# 2012_Carte_Factorisee.net
KiCad netlist of a schematic drawn in Altium Designer
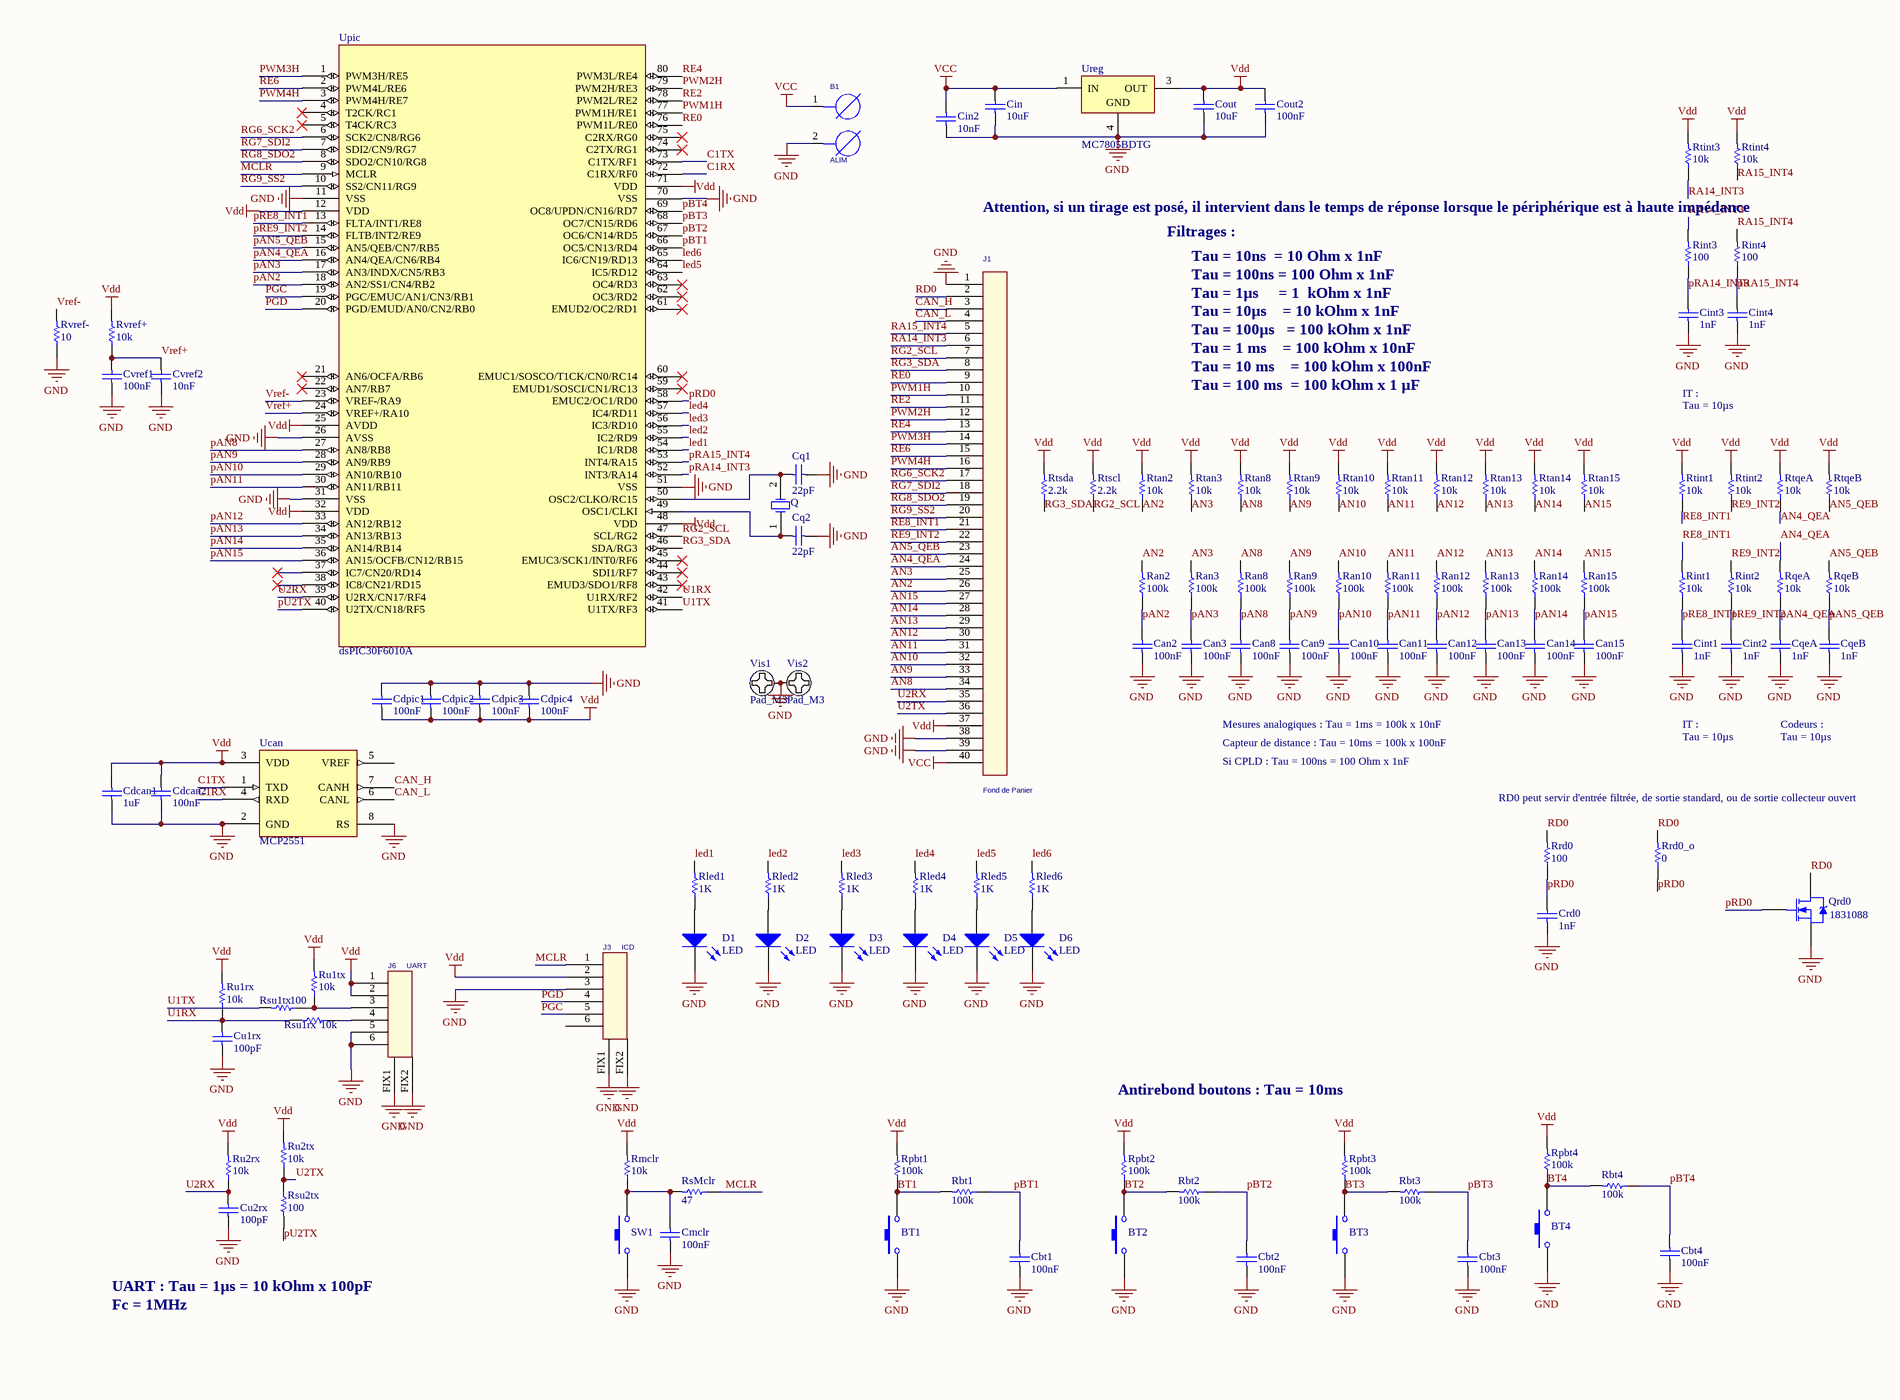
[diagram p0: 2012_Carte_Factorisee.SchDoc, left]
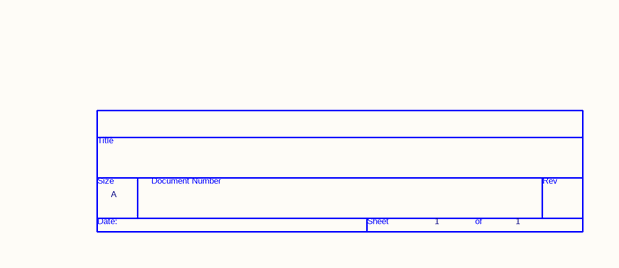
[diagram p1: 2012_Carte_Factorisee.SchDoc, right]

(export (version "E")
  (design (tool "Eeschema 10.0.6"))
  (components
    (comp (ref "*")
      (value "TitleBlock0")
      (fields (field (name "PAGE COUNT") "1") (field (name "PAGE NUMBER") "1") (field (name "PAGE SIZE") "A"))
      (libsource (lib "*") (part "TitleBlock0"))
    )
    (comp (ref "B1") (value "ALIM") (footprint "BORNIER2") (libsource (lib "*") (part "BORNIER2")))
    (comp (ref "BT1")
      (value "SW_Pushbutton_6x6mm_Vertical")
      (footprint "Switch 6x6 Vertical")
      (description "Switch tactil 6mm x 6mm Vertical")
      (libsource (lib "DG_Interrupteur") (part "SW_Pushbutton_6x6mm_Vertical"))
    )
    (comp (ref "BT2")
      (value "SW_Pushbutton_6x6mm_Vertical")
      (footprint "Switch 6x6 Vertical")
      (description "Switch tactil 6mm x 6mm Vertical")
      (libsource (lib "DG_Interrupteur") (part "SW_Pushbutton_6x6mm_Vertical"))
    )
    (comp (ref "BT3")
      (value "SW_Pushbutton_6x6mm_Vertical")
      (footprint "Switch 6x6 Vertical")
      (description "Switch tactil 6mm x 6mm Vertical")
      (libsource (lib "DG_Interrupteur") (part "SW_Pushbutton_6x6mm_Vertical"))
    )
    (comp (ref "BT4")
      (value "SW_Pushbutton_6x6mm_Vertical")
      (footprint "Switch 6x6 Vertical")
      (description "Switch tactil 6mm x 6mm Vertical")
      (libsource (lib "DG_Interrupteur") (part "SW_Pushbutton_6x6mm_Vertical"))
    )
    (comp (ref "Can2")
      (value "100nF")
      (footprint "C0805_N")
      (description "Capacitor")
      (libsource (lib "DG_Condensateur") (part "Capacitor"))
    )
    (comp (ref "Can3")
      (value "100nF")
      (footprint "C0805_N")
      (description "Capacitor")
      (libsource (lib "DG_Condensateur") (part "Capacitor"))
    )
    (comp (ref "Can8")
      (value "100nF")
      (footprint "C0805_N")
      (description "Capacitor")
      (libsource (lib "DG_Condensateur") (part "Capacitor"))
    )
    (comp (ref "Can9")
      (value "100nF")
      (footprint "C0805_N")
      (description "Capacitor")
      (libsource (lib "DG_Condensateur") (part "Capacitor"))
    )
    (comp (ref "Can10")
      (value "100nF")
      (footprint "C0805_N")
      (description "Capacitor")
      (libsource (lib "DG_Condensateur") (part "Capacitor"))
    )
    (comp (ref "Can11")
      (value "100nF")
      (footprint "C0805_N")
      (description "Capacitor")
      (libsource (lib "DG_Condensateur") (part "Capacitor"))
    )
    (comp (ref "Can12")
      (value "100nF")
      (footprint "C0805_N")
      (description "Capacitor")
      (libsource (lib "DG_Condensateur") (part "Capacitor"))
    )
    (comp (ref "Can13")
      (value "100nF")
      (footprint "C0805_N")
      (description "Capacitor")
      (libsource (lib "DG_Condensateur") (part "Capacitor"))
    )
    (comp (ref "Can14")
      (value "100nF")
      (footprint "C0805_N")
      (description "Capacitor")
      (libsource (lib "DG_Condensateur") (part "Capacitor"))
    )
    (comp (ref "Can15")
      (value "100nF")
      (footprint "C0805_N")
      (description "Capacitor")
      (libsource (lib "DG_Condensateur") (part "Capacitor"))
    )
    (comp (ref "Cbt1")
      (value "100nF")
      (footprint "C0805_N")
      (description "Capacitor")
      (libsource (lib "DG_Condensateur") (part "Capacitor"))
    )
    (comp (ref "Cbt2")
      (value "100nF")
      (footprint "C0805_N")
      (description "Capacitor")
      (libsource (lib "DG_Condensateur") (part "Capacitor"))
    )
    (comp (ref "Cbt3")
      (value "100nF")
      (footprint "C0805_N")
      (description "Capacitor")
      (libsource (lib "DG_Condensateur") (part "Capacitor"))
    )
    (comp (ref "Cbt4")
      (value "100nF")
      (footprint "C0805_N")
      (description "Capacitor")
      (libsource (lib "DG_Condensateur") (part "Capacitor"))
    )
    (comp (ref "Cdcan1")
      (value "1uF")
      (footprint "C1206_N")
      (description "Capacitor")
      (libsource (lib "DG_Condensateur") (part "Capacitor"))
    )
    (comp (ref "Cdcan2")
      (value "100nF")
      (footprint "C0805_N")
      (description "Capacitor")
      (libsource (lib "DG_Condensateur") (part "Capacitor"))
    )
    (comp (ref "Cdpic1")
      (value "100nF")
      (footprint "C0805_N")
      (description "Capacitor")
      (libsource (lib "DG_Condensateur") (part "Capacitor"))
    )
    (comp (ref "Cdpic2")
      (value "100nF")
      (footprint "C0805_N")
      (description "Capacitor")
      (libsource (lib "DG_Condensateur") (part "Capacitor"))
    )
    (comp (ref "Cdpic3")
      (value "100nF")
      (footprint "C0805_N")
      (description "Capacitor")
      (libsource (lib "DG_Condensateur") (part "Capacitor"))
    )
    (comp (ref "Cdpic4")
      (value "100nF")
      (footprint "C0805_N")
      (description "Capacitor")
      (libsource (lib "DG_Condensateur") (part "Capacitor"))
    )
    (comp (ref "Cin")
      (value "10uF")
      (footprint "C1206_N")
      (description "Capacitor")
      (libsource (lib "DG_Condensateur") (part "Capacitor"))
    )
    (comp (ref "Cin2")
      (value "10nF")
      (footprint "C0805_N")
      (description "Capacitor")
      (libsource (lib "DG_Condensateur") (part "Capacitor"))
    )
    (comp (ref "Cint1")
      (value "1nF")
      (footprint "C0805_N")
      (description "Capacitor")
      (libsource (lib "DG_Condensateur") (part "Capacitor"))
    )
    (comp (ref "Cint2")
      (value "1nF")
      (footprint "C0805_N")
      (description "Capacitor")
      (libsource (lib "DG_Condensateur") (part "Capacitor"))
    )
    (comp (ref "Cint3")
      (value "1nF")
      (footprint "C0805_N")
      (description "Capacitor")
      (libsource (lib "DG_Condensateur") (part "Capacitor"))
    )
    (comp (ref "Cint4")
      (value "1nF")
      (footprint "C0805_N")
      (description "Capacitor")
      (libsource (lib "DG_Condensateur") (part "Capacitor"))
    )
    (comp (ref "Cmclr")
      (value "100nF")
      (footprint "C0805_N")
      (description "Capacitor")
      (libsource (lib "DG_Condensateur") (part "Capacitor"))
    )
    (comp (ref "Cout")
      (value "10uF")
      (footprint "C1206_N")
      (description "Capacitor")
      (libsource (lib "DG_Condensateur") (part "Capacitor"))
    )
    (comp (ref "Cout2")
      (value "100nF")
      (footprint "C0805_N")
      (description "Capacitor")
      (libsource (lib "DG_Condensateur") (part "Capacitor"))
    )
    (comp (ref "Cq1")
      (value "22pF")
      (footprint "C0805_N")
      (description "Capacitor")
      (libsource (lib "DG_Condensateur") (part "Capacitor"))
    )
    (comp (ref "Cq2")
      (value "22pF")
      (footprint "C0805_N")
      (description "Capacitor")
      (libsource (lib "DG_Condensateur") (part "Capacitor"))
    )
    (comp (ref "CqeA")
      (value "1nF")
      (footprint "C0805_N")
      (description "Capacitor")
      (libsource (lib "DG_Condensateur") (part "Capacitor"))
    )
    (comp (ref "CqeB")
      (value "1nF")
      (footprint "C0805_N")
      (description "Capacitor")
      (libsource (lib "DG_Condensateur") (part "Capacitor"))
    )
    (comp (ref "Crd0")
      (value "1nF")
      (footprint "C0805_N")
      (description "Capacitor")
      (libsource (lib "DG_Condensateur") (part "Capacitor"))
    )
    (comp (ref "Cu1rx")
      (value "100pF")
      (footprint "C0805_N")
      (description "Capacitor")
      (libsource (lib "DG_Condensateur") (part "Capacitor"))
    )
    (comp (ref "Cu2rx")
      (value "100pF")
      (footprint "C0805_N")
      (description "Capacitor")
      (libsource (lib "DG_Condensateur") (part "Capacitor"))
    )
    (comp (ref "Cvref1")
      (value "100nF")
      (footprint "C0805_N")
      (description "Capacitor")
      (libsource (lib "DG_Condensateur") (part "Capacitor"))
    )
    (comp (ref "Cvref2")
      (value "10nF")
      (footprint "C0805_N")
      (description "Capacitor")
      (libsource (lib "DG_Condensateur") (part "Capacitor"))
    )
    (comp (ref "D1")
      (value "LED")
      (footprint "LED_3mm")
      (description "Typical LED")
      (libsource (lib "DG_LED") (part "LED"))
    )
    (comp (ref "D2")
      (value "LED")
      (footprint "LED_3mm")
      (description "Typical LED")
      (libsource (lib "DG_LED") (part "LED"))
    )
    (comp (ref "D3")
      (value "LED")
      (footprint "LED_3mm")
      (description "Typical LED")
      (libsource (lib "DG_LED") (part "LED"))
    )
    (comp (ref "D4")
      (value "LED")
      (footprint "LED_3mm")
      (description "Typical LED")
      (libsource (lib "DG_LED") (part "LED"))
    )
    (comp (ref "D5")
      (value "LED")
      (footprint "LED_3mm")
      (description "Typical LED")
      (libsource (lib "DG_LED") (part "LED"))
    )
    (comp (ref "D6")
      (value "LED")
      (footprint "LED_3mm")
      (description "Typical LED")
      (libsource (lib "DG_LED") (part "LED"))
    )
    (comp (ref "J1")
      (value "Fond de Panier")
      (footprint "HE10/40_FACTO")
      (libsource (lib "*") (part "CONNECTEUR_HE10_40"))
    )
    (comp (ref "J3") (value "ICD") (footprint "RJ11_6/6") (libsource (lib "*") (part "CONNECTEUR_RJ12")))
    (comp (ref "J6") (value "UART") (footprint "RJ11_6/6") (libsource (lib "*") (part "CONNECTEUR_RJ12")))
    (comp (ref "Q")
      (value "QU")
      (footprint "QUARTZ_DROIT_BP")
      (description "Crystal Oscillator")
      (libsource (lib "miniprojet") (part "QUARTZ_DROIT_BAS_PROFIL"))
    )
    (comp (ref "Qrd0")
      (value "~")
      (footprint "SOT23")
      (description "MOSFET N")
      (fields (field (name "FAR") "1831088"))
      (libsource (lib "DG_Transistor") (part "FDP100N10"))
    )
    (comp (ref "Ran2")
      (value "100k")
      (footprint "R1206_N")
      (description "Resistor")
      (libsource (lib "DG_Resistance") (part "Resistor"))
    )
    (comp (ref "Ran3")
      (value "100k")
      (footprint "R1206_N")
      (description "Resistor")
      (libsource (lib "DG_Resistance") (part "Resistor"))
    )
    (comp (ref "Ran8")
      (value "100k")
      (footprint "R1206_N")
      (description "Resistor")
      (libsource (lib "DG_Resistance") (part "Resistor"))
    )
    (comp (ref "Ran9")
      (value "100k")
      (footprint "R1206_N")
      (description "Resistor")
      (libsource (lib "DG_Resistance") (part "Resistor"))
    )
    (comp (ref "Ran10")
      (value "100k")
      (footprint "R1206_N")
      (description "Resistor")
      (libsource (lib "DG_Resistance") (part "Resistor"))
    )
    (comp (ref "Ran11")
      (value "100k")
      (footprint "R1206_N")
      (description "Resistor")
      (libsource (lib "DG_Resistance") (part "Resistor"))
    )
    (comp (ref "Ran12")
      (value "100k")
      (footprint "R1206_N")
      (description "Resistor")
      (libsource (lib "DG_Resistance") (part "Resistor"))
    )
    (comp (ref "Ran13")
      (value "100k")
      (footprint "R1206_N")
      (description "Resistor")
      (libsource (lib "DG_Resistance") (part "Resistor"))
    )
    (comp (ref "Ran14")
      (value "100k")
      (footprint "R1206_N")
      (description "Resistor")
      (libsource (lib "DG_Resistance") (part "Resistor"))
    )
    (comp (ref "Ran15")
      (value "100k")
      (footprint "R1206_N")
      (description "Resistor")
      (libsource (lib "DG_Resistance") (part "Resistor"))
    )
    (comp (ref "Rbt1")
      (value "100k")
      (footprint "R1206_N")
      (description "Resistor")
      (libsource (lib "DG_Resistance") (part "Resistor"))
    )
    (comp (ref "Rbt2")
      (value "100k")
      (footprint "R1206_N")
      (description "Resistor")
      (libsource (lib "DG_Resistance") (part "Resistor"))
    )
    (comp (ref "Rbt3")
      (value "100k")
      (footprint "R1206_N")
      (description "Resistor")
      (libsource (lib "DG_Resistance") (part "Resistor"))
    )
    (comp (ref "Rbt4")
      (value "100k")
      (footprint "R1206_N")
      (description "Resistor")
      (libsource (lib "DG_Resistance") (part "Resistor"))
    )
    (comp (ref "Rint1")
      (value "10k")
      (footprint "R1206_N")
      (description "Resistor")
      (libsource (lib "DG_Resistance") (part "Resistor"))
    )
    (comp (ref "Rint2")
      (value "10k")
      (footprint "R1206_N")
      (description "Resistor")
      (libsource (lib "DG_Resistance") (part "Resistor"))
    )
    (comp (ref "Rint3")
      (value "100")
      (footprint "R1206_N")
      (description "Resistor")
      (libsource (lib "DG_Resistance") (part "Resistor"))
    )
    (comp (ref "Rint4")
      (value "100")
      (footprint "R1206_N")
      (description "Resistor")
      (libsource (lib "DG_Resistance") (part "Resistor"))
    )
    (comp (ref "Rled1")
      (value "1K")
      (footprint "R1206_N")
      (description "Resistor")
      (libsource (lib "DG_Resistance") (part "Resistor"))
    )
    (comp (ref "Rled2")
      (value "1K")
      (footprint "R1206_N")
      (description "Resistor")
      (libsource (lib "DG_Resistance") (part "Resistor"))
    )
    (comp (ref "Rled3")
      (value "1K")
      (footprint "R1206_N")
      (description "Resistor")
      (libsource (lib "DG_Resistance") (part "Resistor"))
    )
    (comp (ref "Rled4")
      (value "1K")
      (footprint "R1206_N")
      (description "Resistor")
      (libsource (lib "DG_Resistance") (part "Resistor"))
    )
    (comp (ref "Rled5")
      (value "1K")
      (footprint "R1206_N")
      (description "Resistor")
      (libsource (lib "DG_Resistance") (part "Resistor"))
    )
    (comp (ref "Rled6")
      (value "1K")
      (footprint "R1206_N")
      (description "Resistor")
      (libsource (lib "DG_Resistance") (part "Resistor"))
    )
    (comp (ref "Rmclr")
      (value "10k")
      (footprint "R1206_N")
      (description "Resistor")
      (libsource (lib "DG_Resistance") (part "Resistor"))
    )
    (comp (ref "Rpbt1")
      (value "100k")
      (footprint "R1206_N")
      (description "Resistor")
      (libsource (lib "DG_Resistance") (part "Resistor"))
    )
    (comp (ref "Rpbt2")
      (value "100k")
      (footprint "R1206_N")
      (description "Resistor")
      (libsource (lib "DG_Resistance") (part "Resistor"))
    )
    (comp (ref "Rpbt3")
      (value "100k")
      (footprint "R1206_N")
      (description "Resistor")
      (libsource (lib "DG_Resistance") (part "Resistor"))
    )
    (comp (ref "Rpbt4")
      (value "100k")
      (footprint "R1206_N")
      (description "Resistor")
      (libsource (lib "DG_Resistance") (part "Resistor"))
    )
    (comp (ref "RqeA")
      (value "10k")
      (footprint "R1206_N")
      (description "Resistor")
      (libsource (lib "DG_Resistance") (part "Resistor"))
    )
    (comp (ref "RqeB")
      (value "10k")
      (footprint "R1206_N")
      (description "Resistor")
      (libsource (lib "DG_Resistance") (part "Resistor"))
    )
    (comp (ref "Rrd0")
      (value "100")
      (footprint "R1206_N")
      (description "Resistor")
      (libsource (lib "DG_Resistance") (part "Resistor"))
    )
    (comp (ref "Rrd0_o")
      (value "0")
      (footprint "R1206_N")
      (description "Resistor")
      (libsource (lib "DG_Resistance") (part "Resistor"))
    )
    (comp (ref "RsMclr")
      (value "47")
      (footprint "R1206_N")
      (description "Resistor")
      (libsource (lib "DG_Resistance") (part "Resistor"))
    )
    (comp (ref "Rsu1rx")
      (value "10k")
      (footprint "R1206_N")
      (description "Resistor")
      (libsource (lib "DG_Resistance") (part "Resistor"))
    )
    (comp (ref "Rsu1tx")
      (value "100")
      (footprint "R1206_N")
      (description "Resistor")
      (libsource (lib "DG_Resistance") (part "Resistor"))
    )
    (comp (ref "Rsu2tx")
      (value "100")
      (footprint "R1206_N")
      (description "Resistor")
      (libsource (lib "DG_Resistance") (part "Resistor"))
    )
    (comp (ref "Rtan2")
      (value "10k")
      (footprint "R1206_N")
      (description "Resistor")
      (libsource (lib "DG_Resistance") (part "Resistor"))
    )
    (comp (ref "Rtan3")
      (value "10k")
      (footprint "R1206_N")
      (description "Resistor")
      (libsource (lib "DG_Resistance") (part "Resistor"))
    )
    (comp (ref "Rtan8")
      (value "10k")
      (footprint "R1206_N")
      (description "Resistor")
      (libsource (lib "DG_Resistance") (part "Resistor"))
    )
    (comp (ref "Rtan9")
      (value "10k")
      (footprint "R1206_N")
      (description "Resistor")
      (libsource (lib "DG_Resistance") (part "Resistor"))
    )
    (comp (ref "Rtan10")
      (value "10k")
      (footprint "R1206_N")
      (description "Resistor")
      (libsource (lib "DG_Resistance") (part "Resistor"))
    )
    (comp (ref "Rtan11")
      (value "10k")
      (footprint "R1206_N")
      (description "Resistor")
      (libsource (lib "DG_Resistance") (part "Resistor"))
    )
    (comp (ref "Rtan12")
      (value "10k")
      (footprint "R1206_N")
      (description "Resistor")
      (libsource (lib "DG_Resistance") (part "Resistor"))
    )
    (comp (ref "Rtan13")
      (value "10k")
      (footprint "R1206_N")
      (description "Resistor")
      (libsource (lib "DG_Resistance") (part "Resistor"))
    )
    (comp (ref "Rtan14")
      (value "10k")
      (footprint "R1206_N")
      (description "Resistor")
      (libsource (lib "DG_Resistance") (part "Resistor"))
    )
    (comp (ref "Rtan15")
      (value "10k")
      (footprint "R1206_N")
      (description "Resistor")
      (libsource (lib "DG_Resistance") (part "Resistor"))
    )
    (comp (ref "Rtint1")
      (value "10k")
      (footprint "R1206_N")
      (description "Resistor")
      (libsource (lib "DG_Resistance") (part "Resistor"))
    )
    (comp (ref "Rtint2")
      (value "10k")
      (footprint "R1206_N")
      (description "Resistor")
      (libsource (lib "DG_Resistance") (part "Resistor"))
    )
    (comp (ref "Rtint3")
      (value "10k")
      (footprint "R1206_N")
      (description "Resistor")
      (libsource (lib "DG_Resistance") (part "Resistor"))
    )
    (comp (ref "Rtint4")
      (value "10k")
      (footprint "R1206_N")
      (description "Resistor")
      (libsource (lib "DG_Resistance") (part "Resistor"))
    )
    (comp (ref "RtqeA")
      (value "10k")
      (footprint "R1206_N")
      (description "Resistor")
      (libsource (lib "DG_Resistance") (part "Resistor"))
    )
    (comp (ref "RtqeB")
      (value "10k")
      (footprint "R1206_N")
      (description "Resistor")
      (libsource (lib "DG_Resistance") (part "Resistor"))
    )
    (comp (ref "Rtscl")
      (value "2.2k")
      (footprint "R1206_N")
      (description "Resistor")
      (libsource (lib "DG_Resistance") (part "Resistor"))
    )
    (comp (ref "Rtsda")
      (value "2.2k")
      (footprint "R1206_N")
      (description "Resistor")
      (libsource (lib "DG_Resistance") (part "Resistor"))
    )
    (comp (ref "Ru1rx")
      (value "10k")
      (footprint "R1206_N")
      (description "Resistor")
      (libsource (lib "DG_Resistance") (part "Resistor"))
    )
    (comp (ref "Ru1tx")
      (value "10k")
      (footprint "R1206_N")
      (description "Resistor")
      (libsource (lib "DG_Resistance") (part "Resistor"))
    )
    (comp (ref "Ru2rx")
      (value "10k")
      (footprint "R1206_N")
      (description "Resistor")
      (libsource (lib "DG_Resistance") (part "Resistor"))
    )
    (comp (ref "Ru2tx")
      (value "10k")
      (footprint "R1206_N")
      (description "Resistor")
      (libsource (lib "DG_Resistance") (part "Resistor"))
    )
    (comp (ref "Rvref+")
      (value "10k")
      (footprint "R1206_N")
      (description "Resistor")
      (libsource (lib "DG_Resistance") (part "Resistor"))
    )
    (comp (ref "Rvref-")
      (value "10")
      (footprint "R1206_N")
      (description "Resistor")
      (libsource (lib "DG_Resistance") (part "Resistor"))
    )
    (comp (ref "SW1")
      (value "SW_Pushbutton_6x6mm_Vertical")
      (footprint "Switch 6x6 Vertical")
      (description "Switch tactil 6mm x 6mm Vertical")
      (libsource (lib "DG_Interrupteur") (part "SW_Pushbutton_6x6mm_Vertical"))
    )
    (comp (ref "Ucan")
      (value "MCP2551")
      (footprint "SOIC150-8_N")
      (description "High Speed Can Transceiver")
      (libsource (lib "Microchip Interface Line Transceiver") (part "MCP2551"))
    )
    (comp (ref "Upic")
      (value "dsPIC30F6010A")
      (footprint "TQFP80_N")
      (description "High-Performance, 16-bit Digital Signal Controllers")
      (libsource (lib "DG_Microcontroleur") (part "dsPIC30F6010A"))
    )
    (comp (ref "Ureg")
      (value "MC7805BDTG")
      (footprint "369A-13")
      (description "Three-Terminal Positive Voltage Regulator")
      (libsource (lib "ON Semi Power Mgt Voltage Regulator") (part "MC7805ACD2T"))
    )
    (comp (ref "Vis1")
      (value "Pad_M3")
      (footprint "M3x6mm")
      (description "Vis M3 X 6mm _TORX_Tête 6mm")
      (libsource (lib "DG_Mecanique") (part "Vis M3 X 6mm _TORX_Tête 6mm"))
    )
    (comp (ref "Vis2")
      (value "Pad_M3")
      (footprint "M3x6mm")
      (description "Vis M3 X 6mm _TORX_Tête 6mm")
      (libsource (lib "DG_Mecanique") (part "Vis M3 X 6mm _TORX_Tête 6mm"))
    )
  )
  (nets
    (net (code "1") (name "/AN2") (class "Default")
      (node (ref "J1") (pin "26") (pinfunction "26_26") (pintype "passive"))
      (node (ref "Ran2") (pin "2") (pinfunction "2_2") (pintype "passive"))
      (node (ref "Rtan2") (pin "1") (pinfunction "1_1") (pintype "passive"))
    )
    (net (code "2") (name "/AN3") (class "Default")
      (node (ref "J1") (pin "25") (pinfunction "25_25") (pintype "passive"))
      (node (ref "Ran3") (pin "2") (pinfunction "2_2") (pintype "passive"))
      (node (ref "Rtan3") (pin "1") (pinfunction "1_1") (pintype "passive"))
    )
    (net (code "3") (name "/AN4_QEA") (class "Default")
      (node (ref "J1") (pin "24") (pinfunction "24_24") (pintype "passive"))
      (node (ref "RqeA") (pin "2") (pinfunction "2_2") (pintype "passive"))
      (node (ref "RtqeA") (pin "1") (pinfunction "1_1") (pintype "passive"))
    )
    (net (code "4") (name "/AN5_QEB") (class "Default")
      (node (ref "J1") (pin "23") (pinfunction "23_23") (pintype "passive"))
      (node (ref "RqeB") (pin "2") (pinfunction "2_2") (pintype "passive"))
      (node (ref "RtqeB") (pin "1") (pinfunction "1_1") (pintype "passive"))
    )
    (net (code "5") (name "/AN8") (class "Default")
      (node (ref "J1") (pin "34") (pinfunction "34_34") (pintype "passive"))
      (node (ref "Ran8") (pin "2") (pinfunction "2_2") (pintype "passive"))
      (node (ref "Rtan8") (pin "1") (pinfunction "1_1") (pintype "passive"))
    )
    (net (code "6") (name "/AN9") (class "Default")
      (node (ref "J1") (pin "33") (pinfunction "33_33") (pintype "passive"))
      (node (ref "Ran9") (pin "2") (pinfunction "2_2") (pintype "passive"))
      (node (ref "Rtan9") (pin "1") (pinfunction "1_1") (pintype "passive"))
    )
    (net (code "7") (name "/AN10") (class "Default")
      (node (ref "J1") (pin "32") (pinfunction "32_32") (pintype "passive"))
      (node (ref "Ran10") (pin "2") (pinfunction "2_2") (pintype "passive"))
      (node (ref "Rtan10") (pin "1") (pinfunction "1_1") (pintype "passive"))
    )
    (net (code "8") (name "/AN11") (class "Default")
      (node (ref "J1") (pin "31") (pinfunction "31_31") (pintype "passive"))
      (node (ref "Ran11") (pin "2") (pinfunction "2_2") (pintype "passive"))
      (node (ref "Rtan11") (pin "1") (pinfunction "1_1") (pintype "passive"))
    )
    (net (code "9") (name "/AN12") (class "Default")
      (node (ref "J1") (pin "30") (pinfunction "30_30") (pintype "passive"))
      (node (ref "Ran12") (pin "2") (pinfunction "2_2") (pintype "passive"))
      (node (ref "Rtan12") (pin "1") (pinfunction "1_1") (pintype "passive"))
    )
    (net (code "10") (name "/AN13") (class "Default")
      (node (ref "J1") (pin "29") (pinfunction "29_29") (pintype "passive"))
      (node (ref "Ran13") (pin "2") (pinfunction "2_2") (pintype "passive"))
      (node (ref "Rtan13") (pin "1") (pinfunction "1_1") (pintype "passive"))
    )
    (net (code "11") (name "/AN14") (class "Default")
      (node (ref "J1") (pin "28") (pinfunction "28_28") (pintype "passive"))
      (node (ref "Ran14") (pin "2") (pinfunction "2_2") (pintype "passive"))
      (node (ref "Rtan14") (pin "1") (pinfunction "1_1") (pintype "passive"))
    )
    (net (code "12") (name "/AN15") (class "Default")
      (node (ref "J1") (pin "27") (pinfunction "27_27") (pintype "passive"))
      (node (ref "Ran15") (pin "2") (pinfunction "2_2") (pintype "passive"))
      (node (ref "Rtan15") (pin "1") (pinfunction "1_1") (pintype "passive"))
    )
    (net (code "13") (name "/BT1") (class "Default")
      (node (ref "BT1") (pin "3") (pinfunction "3_3") (pintype "passive"))
      (node (ref "Rbt1") (pin "2") (pinfunction "2_2") (pintype "passive"))
      (node (ref "Rpbt1") (pin "1") (pinfunction "1_1") (pintype "passive"))
    )
    (net (code "14") (name "/BT2") (class "Default")
      (node (ref "BT2") (pin "3") (pinfunction "3_3") (pintype "passive"))
      (node (ref "Rbt2") (pin "2") (pinfunction "2_2") (pintype "passive"))
      (node (ref "Rpbt2") (pin "1") (pinfunction "1_1") (pintype "passive"))
    )
    (net (code "15") (name "/BT3") (class "Default")
      (node (ref "BT3") (pin "3") (pinfunction "3_3") (pintype "passive"))
      (node (ref "Rbt3") (pin "2") (pinfunction "2_2") (pintype "passive"))
      (node (ref "Rpbt3") (pin "1") (pinfunction "1_1") (pintype "passive"))
    )
    (net (code "16") (name "/BT4") (class "Default")
      (node (ref "BT4") (pin "3") (pinfunction "3_3") (pintype "passive"))
      (node (ref "Rbt4") (pin "2") (pinfunction "2_2") (pintype "passive"))
      (node (ref "Rpbt4") (pin "1") (pinfunction "1_1") (pintype "passive"))
    )
    (net (code "17") (name "/C1RX") (class "Default")
      (node (ref "Ucan") (pin "4") (pinfunction "RXD_4") (pintype "output"))
      (node (ref "Upic") (pin "72") (pinfunction "C1RX/RF0_72") (pintype "bidirectional"))
    )
    (net (code "18") (name "/C1TX") (class "Default")
      (node (ref "Ucan") (pin "1") (pinfunction "TXD_1") (pintype "input"))
      (node (ref "Upic") (pin "73") (pinfunction "C1TX/RF1_73") (pintype "bidirectional"))
    )
    (net (code "19") (name "/CAN_H") (class "Default")
      (node (ref "J1") (pin "3") (pinfunction "3_3") (pintype "passive"))
      (node (ref "Ucan") (pin "7") (pinfunction "CANH_7") (pintype "output"))
    )
    (net (code "20") (name "/CAN_L") (class "Default")
      (node (ref "J1") (pin "4") (pinfunction "4_4") (pintype "passive"))
      (node (ref "Ucan") (pin "6") (pinfunction "CANL_6") (pintype "output"))
    )
    (net (code "21") (name "/MCLR") (class "Default")
      (node (ref "J3") (pin "1") (pinfunction "1_1") (pintype "passive"))
      (node (ref "RsMclr") (pin "1") (pinfunction "1_1") (pintype "passive"))
      (node (ref "Upic") (pin "9") (pinfunction "MCLR_9") (pintype "input"))
    )
    (net (code "22") (name "/PGC") (class "Default")
      (node (ref "J3") (pin "5") (pinfunction "5_5") (pintype "passive"))
      (node (ref "Upic") (pin "19") (pinfunction "PGC/EMUC/AN1/CN3/RB1_19") (pintype "bidirectional"))
    )
    (net (code "23") (name "/PGD") (class "Default")
      (node (ref "J3") (pin "4") (pinfunction "4_4") (pintype "passive"))
      (node (ref "Upic") (pin "20") (pinfunction "PGD/EMUD/AN0/CN2/RB0_20") (pintype "bidirectional"))
    )
    (net (code "24") (name "/PWM1H") (class "Default")
      (node (ref "J1") (pin "10") (pinfunction "10_10") (pintype "passive"))
      (node (ref "Upic") (pin "77") (pinfunction "PWM1H/RE1_77") (pintype "bidirectional"))
    )
    (net (code "25") (name "/PWM2H") (class "Default")
      (node (ref "J1") (pin "12") (pinfunction "12_12") (pintype "passive"))
      (node (ref "Upic") (pin "79") (pinfunction "PWM2H/RE3_79") (pintype "bidirectional"))
    )
    (net (code "26") (name "/PWM3H") (class "Default")
      (node (ref "J1") (pin "14") (pinfunction "14_14") (pintype "passive"))
      (node (ref "Upic") (pin "1") (pinfunction "PWM3H/RE5_1") (pintype "bidirectional"))
    )
    (net (code "27") (name "/PWM4H") (class "Default")
      (node (ref "J1") (pin "16") (pinfunction "16_16") (pintype "passive"))
      (node (ref "Upic") (pin "3") (pinfunction "PWM4H/RE7_3") (pintype "bidirectional"))
    )
    (net (code "28") (name "/RA14_INT3") (class "Default")
      (node (ref "J1") (pin "6") (pinfunction "6_6") (pintype "passive"))
      (node (ref "Rint3") (pin "2") (pinfunction "2_2") (pintype "passive"))
      (node (ref "Rtint3") (pin "1") (pinfunction "1_1") (pintype "passive"))
    )
    (net (code "29") (name "/RA15_INT4") (class "Default")
      (node (ref "J1") (pin "5") (pinfunction "5_5") (pintype "passive"))
      (node (ref "Rint4") (pin "2") (pinfunction "2_2") (pintype "passive"))
      (node (ref "Rtint4") (pin "1") (pinfunction "1_1") (pintype "passive"))
    )
    (net (code "30") (name "/RD0") (class "Default")
      (node (ref "J1") (pin "2") (pinfunction "2_2") (pintype "passive"))
      (node (ref "Qrd0") (pin "3") (pinfunction "D_3") (pintype "passive"))
      (node (ref "Rrd0") (pin "2") (pinfunction "2_2") (pintype "passive"))
      (node (ref "Rrd0_o") (pin "2") (pinfunction "2_2") (pintype "passive"))
    )
    (net (code "31") (name "/RE0") (class "Default")
      (node (ref "J1") (pin "9") (pinfunction "9_9") (pintype "passive"))
      (node (ref "Upic") (pin "76") (pinfunction "PWM1L/RE0_76") (pintype "bidirectional"))
    )
    (net (code "32") (name "/RE2") (class "Default")
      (node (ref "J1") (pin "11") (pinfunction "11_11") (pintype "passive"))
      (node (ref "Upic") (pin "78") (pinfunction "PWM2L/RE2_78") (pintype "bidirectional"))
    )
    (net (code "33") (name "/RE4") (class "Default")
      (node (ref "J1") (pin "13") (pinfunction "13_13") (pintype "passive"))
      (node (ref "Upic") (pin "80") (pinfunction "PWM3L/RE4_80") (pintype "bidirectional"))
    )
    (net (code "34") (name "/RE6") (class "Default")
      (node (ref "J1") (pin "15") (pinfunction "15_15") (pintype "passive"))
      (node (ref "Upic") (pin "2") (pinfunction "PWM4L/RE6_2") (pintype "bidirectional"))
    )
    (net (code "35") (name "/RE8_INT1") (class "Default")
      (node (ref "J1") (pin "21") (pinfunction "21_21") (pintype "passive"))
      (node (ref "Rint1") (pin "2") (pinfunction "2_2") (pintype "passive"))
      (node (ref "Rtint1") (pin "1") (pinfunction "1_1") (pintype "passive"))
    )
    (net (code "36") (name "/RE9_INT2") (class "Default")
      (node (ref "J1") (pin "22") (pinfunction "22_22") (pintype "passive"))
      (node (ref "Rint2") (pin "2") (pinfunction "2_2") (pintype "passive"))
      (node (ref "Rtint2") (pin "1") (pinfunction "1_1") (pintype "passive"))
    )
    (net (code "37") (name "/RG2_SCL") (class "Default")
      (node (ref "J1") (pin "7") (pinfunction "7_7") (pintype "passive"))
      (node (ref "Rtscl") (pin "1") (pinfunction "1_1") (pintype "passive"))
      (node (ref "Upic") (pin "47") (pinfunction "SCL/RG2_47") (pintype "bidirectional"))
    )
    (net (code "38") (name "/RG3_SDA") (class "Default")
      (node (ref "J1") (pin "8") (pinfunction "8_8") (pintype "passive"))
      (node (ref "Rtsda") (pin "1") (pinfunction "1_1") (pintype "passive"))
      (node (ref "Upic") (pin "46") (pinfunction "SDA/RG3_46") (pintype "bidirectional"))
    )
    (net (code "39") (name "/RG6_SCK2") (class "Default")
      (node (ref "J1") (pin "17") (pinfunction "17_17") (pintype "passive"))
      (node (ref "Upic") (pin "6") (pinfunction "SCK2/CN8/RG6_6") (pintype "bidirectional"))
    )
    (net (code "40") (name "/RG7_SDI2") (class "Default")
      (node (ref "J1") (pin "18") (pinfunction "18_18") (pintype "passive"))
      (node (ref "Upic") (pin "7") (pinfunction "SDI2/CN9/RG7_7") (pintype "bidirectional"))
    )
    (net (code "41") (name "/RG8_SDO2") (class "Default")
      (node (ref "J1") (pin "19") (pinfunction "19_19") (pintype "passive"))
      (node (ref "Upic") (pin "8") (pinfunction "SDO2/CN10/RG8_8") (pintype "bidirectional"))
    )
    (net (code "42") (name "/RG9_SS2") (class "Default")
      (node (ref "J1") (pin "20") (pinfunction "20_20") (pintype "passive"))
      (node (ref "Upic") (pin "10") (pinfunction "SS2/CN11/RG9_10") (pintype "bidirectional"))
    )
    (net (code "43") (name "/U1RX") (class "Default")
      (node (ref "Cu1rx") (pin "2") (pinfunction "2_2") (pintype "passive"))
      (node (ref "Rsu1rx") (pin "2") (pinfunction "2_2") (pintype "passive"))
      (node (ref "Ru1rx") (pin "1") (pinfunction "1_1") (pintype "passive"))
      (node (ref "Upic") (pin "42") (pinfunction "U1RX/RF2_42") (pintype "bidirectional"))
    )
    (net (code "44") (name "/U1TX") (class "Default")
      (node (ref "Rsu1tx") (pin "2") (pinfunction "2_2") (pintype "passive"))
      (node (ref "Upic") (pin "41") (pinfunction "U1TX/RF3_41") (pintype "bidirectional"))
    )
    (net (code "45") (name "/U2RX") (class "Default")
      (node (ref "Cu2rx") (pin "2") (pinfunction "2_2") (pintype "passive"))
      (node (ref "J1") (pin "35") (pinfunction "35_35") (pintype "passive"))
      (node (ref "Ru2rx") (pin "1") (pinfunction "1_1") (pintype "passive"))
      (node (ref "Upic") (pin "39") (pinfunction "U2RX/CN17/RF4_39") (pintype "bidirectional"))
    )
    (net (code "46") (name "/U2TX") (class "Default")
      (node (ref "J1") (pin "36") (pinfunction "36_36") (pintype "passive"))
      (node (ref "Rsu2tx") (pin "1") (pinfunction "1_1") (pintype "passive"))
      (node (ref "Ru2tx") (pin "1") (pinfunction "1_1") (pintype "passive"))
    )
    (net (code "47") (name "/Vref+") (class "Default")
      (node (ref "Cvref1") (pin "2") (pinfunction "2_2") (pintype "passive"))
      (node (ref "Cvref2") (pin "2") (pinfunction "2_2") (pintype "passive"))
      (node (ref "Rvref+") (pin "1") (pinfunction "1_1") (pintype "passive"))
      (node (ref "Upic") (pin "24") (pinfunction "VREF+/RA10_24") (pintype "bidirectional"))
    )
    (net (code "48") (name "/Vref-") (class "Default")
      (node (ref "Rvref-") (pin "2") (pinfunction "2_2") (pintype "passive"))
      (node (ref "Upic") (pin "23") (pinfunction "VREF-/RA9_23") (pintype "bidirectional"))
    )
    (net (code "49") (name "/led1") (class "Default")
      (node (ref "Rled1") (pin "2") (pinfunction "2_2") (pintype "passive"))
      (node (ref "Upic") (pin "54") (pinfunction "IC1/RD8_54") (pintype "bidirectional"))
    )
    (net (code "50") (name "/led2") (class "Default")
      (node (ref "Rled2") (pin "2") (pinfunction "2_2") (pintype "passive"))
      (node (ref "Upic") (pin "55") (pinfunction "IC2/RD9_55") (pintype "bidirectional"))
    )
    (net (code "51") (name "/led3") (class "Default")
      (node (ref "Rled3") (pin "2") (pinfunction "2_2") (pintype "passive"))
      (node (ref "Upic") (pin "56") (pinfunction "IC3/RD10_56") (pintype "bidirectional"))
    )
    (net (code "52") (name "/led4") (class "Default")
      (node (ref "Rled4") (pin "2") (pinfunction "2_2") (pintype "passive"))
      (node (ref "Upic") (pin "57") (pinfunction "IC4/RD11_57") (pintype "bidirectional"))
    )
    (net (code "53") (name "/led5") (class "Default")
      (node (ref "Rled5") (pin "2") (pinfunction "2_2") (pintype "passive"))
      (node (ref "Upic") (pin "64") (pinfunction "IC5/RD12_64") (pintype "bidirectional"))
    )
    (net (code "54") (name "/led6") (class "Default")
      (node (ref "Rled6") (pin "2") (pinfunction "2_2") (pintype "passive"))
      (node (ref "Upic") (pin "65") (pinfunction "IC6/CN19/RD13_65") (pintype "bidirectional"))
    )
    (net (code "55") (name "/pAN2") (class "Default")
      (node (ref "Can2") (pin "2") (pinfunction "2_2") (pintype "passive"))
      (node (ref "Ran2") (pin "1") (pinfunction "1_1") (pintype "passive"))
      (node (ref "Upic") (pin "18") (pinfunction "AN2/SS1/CN4/RB2_18") (pintype "bidirectional"))
    )
    (net (code "56") (name "/pAN3") (class "Default")
      (node (ref "Can3") (pin "2") (pinfunction "2_2") (pintype "passive"))
      (node (ref "Ran3") (pin "1") (pinfunction "1_1") (pintype "passive"))
      (node (ref "Upic") (pin "17") (pinfunction "AN3/INDX/CN5/RB3_17") (pintype "bidirectional"))
    )
    (net (code "57") (name "/pAN4_QEA") (class "Default")
      (node (ref "CqeA") (pin "2") (pinfunction "2_2") (pintype "passive"))
      (node (ref "RqeA") (pin "1") (pinfunction "1_1") (pintype "passive"))
      (node (ref "Upic") (pin "16") (pinfunction "AN4/QEA/CN6/RB4_16") (pintype "bidirectional"))
    )
    (net (code "58") (name "/pAN5_QEB") (class "Default")
      (node (ref "CqeB") (pin "2") (pinfunction "2_2") (pintype "passive"))
      (node (ref "RqeB") (pin "1") (pinfunction "1_1") (pintype "passive"))
      (node (ref "Upic") (pin "15") (pinfunction "AN5/QEB/CN7/RB5_15") (pintype "bidirectional"))
    )
    (net (code "59") (name "/pAN8") (class "Default")
      (node (ref "Can8") (pin "2") (pinfunction "2_2") (pintype "passive"))
      (node (ref "Ran8") (pin "1") (pinfunction "1_1") (pintype "passive"))
      (node (ref "Upic") (pin "27") (pinfunction "AN8/RB8_27") (pintype "bidirectional"))
    )
    (net (code "60") (name "/pAN9") (class "Default")
      (node (ref "Can9") (pin "2") (pinfunction "2_2") (pintype "passive"))
      (node (ref "Ran9") (pin "1") (pinfunction "1_1") (pintype "passive"))
      (node (ref "Upic") (pin "28") (pinfunction "AN9/RB9_28") (pintype "bidirectional"))
    )
    (net (code "61") (name "/pAN10") (class "Default")
      (node (ref "Can10") (pin "2") (pinfunction "2_2") (pintype "passive"))
      (node (ref "Ran10") (pin "1") (pinfunction "1_1") (pintype "passive"))
      (node (ref "Upic") (pin "29") (pinfunction "AN10/RB10_29") (pintype "bidirectional"))
    )
    (net (code "62") (name "/pAN11") (class "Default")
      (node (ref "Can11") (pin "2") (pinfunction "2_2") (pintype "passive"))
      (node (ref "Ran11") (pin "1") (pinfunction "1_1") (pintype "passive"))
      (node (ref "Upic") (pin "30") (pinfunction "AN11/RB11_30") (pintype "bidirectional"))
    )
    (net (code "63") (name "/pAN12") (class "Default")
      (node (ref "Can12") (pin "2") (pinfunction "2_2") (pintype "passive"))
      (node (ref "Ran12") (pin "1") (pinfunction "1_1") (pintype "passive"))
      (node (ref "Upic") (pin "33") (pinfunction "AN12/RB12_33") (pintype "bidirectional"))
    )
    (net (code "64") (name "/pAN13") (class "Default")
      (node (ref "Can13") (pin "2") (pinfunction "2_2") (pintype "passive"))
      (node (ref "Ran13") (pin "1") (pinfunction "1_1") (pintype "passive"))
      (node (ref "Upic") (pin "34") (pinfunction "AN13/RB13_34") (pintype "bidirectional"))
    )
    (net (code "65") (name "/pAN14") (class "Default")
      (node (ref "Can14") (pin "2") (pinfunction "2_2") (pintype "passive"))
      (node (ref "Ran14") (pin "1") (pinfunction "1_1") (pintype "passive"))
      (node (ref "Upic") (pin "35") (pinfunction "AN14/RB14_35") (pintype "bidirectional"))
    )
    (net (code "66") (name "/pAN15") (class "Default")
      (node (ref "Can15") (pin "2") (pinfunction "2_2") (pintype "passive"))
      (node (ref "Ran15") (pin "1") (pinfunction "1_1") (pintype "passive"))
      (node (ref "Upic") (pin "36") (pinfunction "AN15/OCFB/CN12/RB15_36") (pintype "bidirectional"))
    )
    (net (code "67") (name "/pBT1") (class "Default")
      (node (ref "Cbt1") (pin "2") (pinfunction "2_2") (pintype "passive"))
      (node (ref "Rbt1") (pin "1") (pinfunction "1_1") (pintype "passive"))
      (node (ref "Upic") (pin "66") (pinfunction "OC5/CN13/RD4_66") (pintype "bidirectional"))
    )
    (net (code "68") (name "/pBT2") (class "Default")
      (node (ref "Cbt2") (pin "2") (pinfunction "2_2") (pintype "passive"))
      (node (ref "Rbt2") (pin "1") (pinfunction "1_1") (pintype "passive"))
      (node (ref "Upic") (pin "67") (pinfunction "OC6/CN14/RD5_67") (pintype "bidirectional"))
    )
    (net (code "69") (name "/pBT3") (class "Default")
      (node (ref "Cbt3") (pin "2") (pinfunction "2_2") (pintype "passive"))
      (node (ref "Rbt3") (pin "1") (pinfunction "1_1") (pintype "passive"))
      (node (ref "Upic") (pin "68") (pinfunction "OC7/CN15/RD6_68") (pintype "bidirectional"))
    )
    (net (code "70") (name "/pBT4") (class "Default")
      (node (ref "Cbt4") (pin "2") (pinfunction "2_2") (pintype "passive"))
      (node (ref "Rbt4") (pin "1") (pinfunction "1_1") (pintype "passive"))
      (node (ref "Upic") (pin "69") (pinfunction "OC8/UPDN/CN16/RD7_69") (pintype "bidirectional"))
    )
    (net (code "71") (name "/pRA14_INT3") (class "Default")
      (node (ref "Cint3") (pin "2") (pinfunction "2_2") (pintype "passive"))
      (node (ref "Rint3") (pin "1") (pinfunction "1_1") (pintype "passive"))
      (node (ref "Upic") (pin "52") (pinfunction "INT3/RA14_52") (pintype "bidirectional"))
    )
    (net (code "72") (name "/pRA15_INT4") (class "Default")
      (node (ref "Cint4") (pin "2") (pinfunction "2_2") (pintype "passive"))
      (node (ref "Rint4") (pin "1") (pinfunction "1_1") (pintype "passive"))
      (node (ref "Upic") (pin "53") (pinfunction "INT4/RA15_53") (pintype "bidirectional"))
    )
    (net (code "73") (name "/pRD0") (class "Default")
      (node (ref "Crd0") (pin "2") (pinfunction "2_2") (pintype "passive"))
      (node (ref "Qrd0") (pin "1") (pinfunction "G_1") (pintype "passive"))
      (node (ref "Rrd0") (pin "1") (pinfunction "1_1") (pintype "passive"))
      (node (ref "Rrd0_o") (pin "1") (pinfunction "1_1") (pintype "passive"))
      (node (ref "Upic") (pin "58") (pinfunction "EMUC2/OC1/RD0_58") (pintype "bidirectional"))
    )
    (net (code "74") (name "/pRE8_INT1") (class "Default")
      (node (ref "Cint1") (pin "2") (pinfunction "2_2") (pintype "passive"))
      (node (ref "Rint1") (pin "1") (pinfunction "1_1") (pintype "passive"))
      (node (ref "Upic") (pin "13") (pinfunction "FLTA/INT1/RE8_13") (pintype "bidirectional"))
    )
    (net (code "75") (name "/pRE9_INT2") (class "Default")
      (node (ref "Cint2") (pin "2") (pinfunction "2_2") (pintype "passive"))
      (node (ref "Rint2") (pin "1") (pinfunction "1_1") (pintype "passive"))
      (node (ref "Upic") (pin "14") (pinfunction "FLTB/INT2/RE9_14") (pintype "bidirectional"))
    )
    (net (code "76") (name "/pU2TX") (class "Default")
      (node (ref "Rsu2tx") (pin "2") (pinfunction "2_2") (pintype "passive"))
      (node (ref "Upic") (pin "40") (pinfunction "U2TX/CN18/RF5_40") (pintype "bidirectional"))
    )
    (net (code "77") (name "GND") (class "Default")
      (node (ref "B1") (pin "2") (pinfunction "B2_2") (pintype "passive"))
      (node (ref "BT1") (pin "1") (pinfunction "1_1") (pintype "passive"))
      (node (ref "BT2") (pin "1") (pinfunction "1_1") (pintype "passive"))
      (node (ref "BT3") (pin "1") (pinfunction "1_1") (pintype "passive"))
      (node (ref "BT4") (pin "1") (pinfunction "1_1") (pintype "passive"))
      (node (ref "Can10") (pin "1") (pinfunction "1_1") (pintype "passive"))
      (node (ref "Can11") (pin "1") (pinfunction "1_1") (pintype "passive"))
      (node (ref "Can12") (pin "1") (pinfunction "1_1") (pintype "passive"))
      (node (ref "Can13") (pin "1") (pinfunction "1_1") (pintype "passive"))
      (node (ref "Can14") (pin "1") (pinfunction "1_1") (pintype "passive"))
      (node (ref "Can15") (pin "1") (pinfunction "1_1") (pintype "passive"))
      (node (ref "Can2") (pin "1") (pinfunction "1_1") (pintype "passive"))
      (node (ref "Can3") (pin "1") (pinfunction "1_1") (pintype "passive"))
      (node (ref "Can8") (pin "1") (pinfunction "1_1") (pintype "passive"))
      (node (ref "Can9") (pin "1") (pinfunction "1_1") (pintype "passive"))
      (node (ref "Cbt1") (pin "1") (pinfunction "1_1") (pintype "passive"))
      (node (ref "Cbt2") (pin "1") (pinfunction "1_1") (pintype "passive"))
      (node (ref "Cbt3") (pin "1") (pinfunction "1_1") (pintype "passive"))
      (node (ref "Cbt4") (pin "1") (pinfunction "1_1") (pintype "passive"))
      (node (ref "Cdcan1") (pin "1") (pinfunction "1_1") (pintype "passive"))
      (node (ref "Cdcan2") (pin "1") (pinfunction "1_1") (pintype "passive"))
      (node (ref "Cdpic1") (pin "2") (pinfunction "2_2") (pintype "passive"))
      (node (ref "Cdpic2") (pin "2") (pinfunction "2_2") (pintype "passive"))
      (node (ref "Cdpic3") (pin "2") (pinfunction "2_2") (pintype "passive"))
      (node (ref "Cdpic4") (pin "2") (pinfunction "2_2") (pintype "passive"))
      (node (ref "Cin") (pin "1") (pinfunction "1_1") (pintype "passive"))
      (node (ref "Cin2") (pin "1") (pinfunction "1_1") (pintype "passive"))
      (node (ref "Cint1") (pin "1") (pinfunction "1_1") (pintype "passive"))
      (node (ref "Cint2") (pin "1") (pinfunction "1_1") (pintype "passive"))
      (node (ref "Cint3") (pin "1") (pinfunction "1_1") (pintype "passive"))
      (node (ref "Cint4") (pin "1") (pinfunction "1_1") (pintype "passive"))
      (node (ref "Cmclr") (pin "1") (pinfunction "1_1") (pintype "passive"))
      (node (ref "Cout") (pin "1") (pinfunction "1_1") (pintype "passive"))
      (node (ref "Cout2") (pin "1") (pinfunction "1_1") (pintype "passive"))
      (node (ref "Cq1") (pin "2") (pinfunction "2_2") (pintype "passive"))
      (node (ref "Cq2") (pin "2") (pinfunction "2_2") (pintype "passive"))
      (node (ref "CqeA") (pin "1") (pinfunction "1_1") (pintype "passive"))
      (node (ref "CqeB") (pin "1") (pinfunction "1_1") (pintype "passive"))
      (node (ref "Crd0") (pin "1") (pinfunction "1_1") (pintype "passive"))
      (node (ref "Cu1rx") (pin "1") (pinfunction "1_1") (pintype "passive"))
      (node (ref "Cu2rx") (pin "1") (pinfunction "1_1") (pintype "passive"))
      (node (ref "Cvref1") (pin "1") (pinfunction "1_1") (pintype "passive"))
      (node (ref "Cvref2") (pin "1") (pinfunction "1_1") (pintype "passive"))
      (node (ref "D1") (pin "2") (pinfunction "2_2") (pintype "passive"))
      (node (ref "D2") (pin "2") (pinfunction "2_2") (pintype "passive"))
      (node (ref "D3") (pin "2") (pinfunction "2_2") (pintype "passive"))
      (node (ref "D4") (pin "2") (pinfunction "2_2") (pintype "passive"))
      (node (ref "D5") (pin "2") (pinfunction "2_2") (pintype "passive"))
      (node (ref "D6") (pin "2") (pinfunction "2_2") (pintype "passive"))
      (node (ref "J1") (pin "1") (pinfunction "1_1") (pintype "passive"))
      (node (ref "J1") (pin "38") (pinfunction "38_38") (pintype "passive"))
      (node (ref "J1") (pin "39") (pinfunction "39_39") (pintype "passive"))
      (node (ref "J3") (pin "3") (pinfunction "3_3") (pintype "passive"))
      (node (ref "J3") (pin "FIX1") (pinfunction "FIX1_FIX1") (pintype "passive"))
      (node (ref "J3") (pin "FIX2") (pinfunction "FIX2_FIX2") (pintype "passive"))
      (node (ref "J6") (pin "5") (pinfunction "5_5") (pintype "passive"))
      (node (ref "J6") (pin "6") (pinfunction "6_6") (pintype "passive"))
      (node (ref "J6") (pin "FIX1") (pinfunction "FIX1_FIX1") (pintype "passive"))
      (node (ref "J6") (pin "FIX2") (pinfunction "FIX2_FIX2") (pintype "passive"))
      (node (ref "Qrd0") (pin "2") (pinfunction "S_2") (pintype "passive"))
      (node (ref "Rvref-") (pin "1") (pinfunction "1_1") (pintype "passive"))
      (node (ref "SW1") (pin "1") (pinfunction "1_1") (pintype "passive"))
      (node (ref "Ucan") (pin "2") (pinfunction "GND_2") (pintype "power_in"))
      (node (ref "Ucan") (pin "8") (pinfunction "RS_8") (pintype "passive"))
      (node (ref "Upic") (pin "11") (pinfunction "VSS_11") (pintype "power_in"))
      (node (ref "Upic") (pin "26") (pinfunction "AVSS_26") (pintype "power_in"))
      (node (ref "Upic") (pin "31") (pinfunction "VSS_31") (pintype "power_in"))
      (node (ref "Upic") (pin "51") (pinfunction "VSS_51") (pintype "power_in"))
      (node (ref "Upic") (pin "70") (pinfunction "VSS_70") (pintype "power_in"))
      (node (ref "Ureg") (pin "4") (pinfunction "GND_4") (pintype "power_in"))
      (node (ref "Vis1") (pin "1") (pinfunction "1_1") (pintype "passive"))
      (node (ref "Vis2") (pin "1") (pinfunction "1_1") (pintype "passive"))
    )
    (net (code "78") (name "Net-(Cmclr-Pad2)") (class "Default")
      (node (ref "Cmclr") (pin "2") (pinfunction "2_2") (pintype "passive"))
      (node (ref "Rmclr") (pin "1") (pinfunction "1_1") (pintype "passive"))
      (node (ref "RsMclr") (pin "2") (pinfunction "2_2") (pintype "passive"))
      (node (ref "SW1") (pin "3") (pinfunction "3_3") (pintype "passive"))
    )
    (net (code "79") (name "Net-(D1-Pad1)") (class "Default")
      (node (ref "D1") (pin "1") (pinfunction "1_1") (pintype "passive"))
      (node (ref "Rled1") (pin "1") (pinfunction "1_1") (pintype "passive"))
    )
    (net (code "80") (name "Net-(D2-Pad1)") (class "Default")
      (node (ref "D2") (pin "1") (pinfunction "1_1") (pintype "passive"))
      (node (ref "Rled2") (pin "1") (pinfunction "1_1") (pintype "passive"))
    )
    (net (code "81") (name "Net-(D3-Pad1)") (class "Default")
      (node (ref "D3") (pin "1") (pinfunction "1_1") (pintype "passive"))
      (node (ref "Rled3") (pin "1") (pinfunction "1_1") (pintype "passive"))
    )
    (net (code "82") (name "Net-(D4-Pad1)") (class "Default")
      (node (ref "D4") (pin "1") (pinfunction "1_1") (pintype "passive"))
      (node (ref "Rled4") (pin "1") (pinfunction "1_1") (pintype "passive"))
    )
    (net (code "83") (name "Net-(D5-Pad1)") (class "Default")
      (node (ref "D5") (pin "1") (pinfunction "1_1") (pintype "passive"))
      (node (ref "Rled5") (pin "1") (pinfunction "1_1") (pintype "passive"))
    )
    (net (code "84") (name "Net-(D6-Pad1)") (class "Default")
      (node (ref "D6") (pin "1") (pinfunction "1_1") (pintype "passive"))
      (node (ref "Rled6") (pin "1") (pinfunction "1_1") (pintype "passive"))
    )
    (net (code "85") (name "Net-(J6-Pad3)") (class "Default")
      (node (ref "J6") (pin "3") (pinfunction "3_3") (pintype "passive"))
      (node (ref "Rsu1tx") (pin "1") (pinfunction "1_1") (pintype "passive"))
      (node (ref "Ru1tx") (pin "1") (pinfunction "1_1") (pintype "passive"))
    )
    (net (code "86") (name "Net-(J6-Pad4)") (class "Default")
      (node (ref "J6") (pin "4") (pinfunction "4_4") (pintype "passive"))
      (node (ref "Rsu1rx") (pin "1") (pinfunction "1_1") (pintype "passive"))
    )
    (net (code "87") (name "Net-(Q-OSC1)") (class "Default")
      (node (ref "Cq2") (pin "1") (pinfunction "1_1") (pintype "passive"))
      (node (ref "Q") (pin "1") (pinfunction "OSC1_1") (pintype "passive"))
      (node (ref "Upic") (pin "49") (pinfunction "OSC1/CLKI_49") (pintype "input"))
    )
    (net (code "88") (name "Net-(Q-OSC2)") (class "Default")
      (node (ref "Cq1") (pin "1") (pinfunction "1_1") (pintype "passive"))
      (node (ref "Q") (pin "2") (pinfunction "OSC2_2") (pintype "passive"))
      (node (ref "Upic") (pin "50") (pinfunction "OSC2/CLKO/RC15_50") (pintype "bidirectional"))
    )
    (net (code "89") (name "VCC") (class "Default")
      (node (ref "B1") (pin "1") (pinfunction "B1_1") (pintype "passive"))
      (node (ref "Cin") (pin "2") (pinfunction "2_2") (pintype "passive"))
      (node (ref "Cin2") (pin "2") (pinfunction "2_2") (pintype "passive"))
      (node (ref "J1") (pin "40") (pinfunction "40_40") (pintype "passive"))
      (node (ref "Ureg") (pin "1") (pinfunction "IN_1") (pintype "power_in"))
    )
    (net (code "90") (name "Vdd") (class "Default")
      (node (ref "Cdcan1") (pin "2") (pinfunction "2_2") (pintype "passive"))
      (node (ref "Cdcan2") (pin "2") (pinfunction "2_2") (pintype "passive"))
      (node (ref "Cdpic1") (pin "1") (pinfunction "1_1") (pintype "passive"))
      (node (ref "Cdpic2") (pin "1") (pinfunction "1_1") (pintype "passive"))
      (node (ref "Cdpic3") (pin "1") (pinfunction "1_1") (pintype "passive"))
      (node (ref "Cdpic4") (pin "1") (pinfunction "1_1") (pintype "passive"))
      (node (ref "Cout") (pin "2") (pinfunction "2_2") (pintype "passive"))
      (node (ref "Cout2") (pin "2") (pinfunction "2_2") (pintype "passive"))
      (node (ref "J1") (pin "37") (pinfunction "37_37") (pintype "passive"))
      (node (ref "J3") (pin "2") (pinfunction "2_2") (pintype "passive"))
      (node (ref "J6") (pin "1") (pinfunction "1_1") (pintype "passive"))
      (node (ref "J6") (pin "2") (pinfunction "2_2") (pintype "passive"))
      (node (ref "Rmclr") (pin "2") (pinfunction "2_2") (pintype "passive"))
      (node (ref "Rpbt1") (pin "2") (pinfunction "2_2") (pintype "passive"))
      (node (ref "Rpbt2") (pin "2") (pinfunction "2_2") (pintype "passive"))
      (node (ref "Rpbt3") (pin "2") (pinfunction "2_2") (pintype "passive"))
      (node (ref "Rpbt4") (pin "2") (pinfunction "2_2") (pintype "passive"))
      (node (ref "Rtan10") (pin "2") (pinfunction "2_2") (pintype "passive"))
      (node (ref "Rtan11") (pin "2") (pinfunction "2_2") (pintype "passive"))
      (node (ref "Rtan12") (pin "2") (pinfunction "2_2") (pintype "passive"))
      (node (ref "Rtan13") (pin "2") (pinfunction "2_2") (pintype "passive"))
      (node (ref "Rtan14") (pin "2") (pinfunction "2_2") (pintype "passive"))
      (node (ref "Rtan15") (pin "2") (pinfunction "2_2") (pintype "passive"))
      (node (ref "Rtan2") (pin "2") (pinfunction "2_2") (pintype "passive"))
      (node (ref "Rtan3") (pin "2") (pinfunction "2_2") (pintype "passive"))
      (node (ref "Rtan8") (pin "2") (pinfunction "2_2") (pintype "passive"))
      (node (ref "Rtan9") (pin "2") (pinfunction "2_2") (pintype "passive"))
      (node (ref "Rtint1") (pin "2") (pinfunction "2_2") (pintype "passive"))
      (node (ref "Rtint2") (pin "2") (pinfunction "2_2") (pintype "passive"))
      (node (ref "Rtint3") (pin "2") (pinfunction "2_2") (pintype "passive"))
      (node (ref "Rtint4") (pin "2") (pinfunction "2_2") (pintype "passive"))
      (node (ref "RtqeA") (pin "2") (pinfunction "2_2") (pintype "passive"))
      (node (ref "RtqeB") (pin "2") (pinfunction "2_2") (pintype "passive"))
      (node (ref "Rtscl") (pin "2") (pinfunction "2_2") (pintype "passive"))
      (node (ref "Rtsda") (pin "2") (pinfunction "2_2") (pintype "passive"))
      (node (ref "Ru1rx") (pin "2") (pinfunction "2_2") (pintype "passive"))
      (node (ref "Ru1tx") (pin "2") (pinfunction "2_2") (pintype "passive"))
      (node (ref "Ru2rx") (pin "2") (pinfunction "2_2") (pintype "passive"))
      (node (ref "Ru2tx") (pin "2") (pinfunction "2_2") (pintype "passive"))
      (node (ref "Rvref+") (pin "2") (pinfunction "2_2") (pintype "passive"))
      (node (ref "Ucan") (pin "3") (pinfunction "VDD_3") (pintype "power_in"))
      (node (ref "Upic") (pin "12") (pinfunction "VDD_12") (pintype "power_in"))
      (node (ref "Upic") (pin "25") (pinfunction "AVDD_25") (pintype "power_in"))
      (node (ref "Upic") (pin "32") (pinfunction "VDD_32") (pintype "power_in"))
      (node (ref "Upic") (pin "48") (pinfunction "VDD_48") (pintype "power_in"))
      (node (ref "Upic") (pin "71") (pinfunction "VDD_71") (pintype "power_in"))
      (node (ref "Ureg") (pin "3") (pinfunction "OUT_3") (pintype "power_in"))
    )
    (net (code "91") (name "unconnected-(J3-Pad6)") (class "Default")
      (node (ref "J3") (pin "6") (pinfunction "6_6") (pintype "passive"))
    )
    (net (code "92") (name "unconnected-(Ucan-VREF-Pad5)") (class "Default")
      (node (ref "Ucan") (pin "5") (pinfunction "VREF_5") (pintype "output"))
    )
    (net (code "93") (name "unconnected-(Upic-AN6{slash}OCFA{slash}RB6-Pad21)") (class "Default")
      (node (ref "Upic") (pin "21") (pinfunction "AN6/OCFA/RB6_21") (pintype "bidirectional+no_connect"))
    )
    (net (code "94") (name "unconnected-(Upic-AN7{slash}RB7-Pad22)") (class "Default")
      (node (ref "Upic") (pin "22") (pinfunction "AN7/RB7_22") (pintype "bidirectional+no_connect"))
    )
    (net (code "95") (name "unconnected-(Upic-C2RX{slash}RG0-Pad75)") (class "Default")
      (node (ref "Upic") (pin "75") (pinfunction "C2RX/RG0_75") (pintype "bidirectional+no_connect"))
    )
    (net (code "96") (name "unconnected-(Upic-C2TX{slash}RG1-Pad74)") (class "Default")
      (node (ref "Upic") (pin "74") (pinfunction "C2TX/RG1_74") (pintype "bidirectional+no_connect"))
    )
    (net (code "97") (name "unconnected-(Upic-EMUC1{slash}SOSCO{slash}T1CK{slash}CN0{slash}RC14-Pad60)") (class "Default")
      (node (ref "Upic") (pin "60") (pinfunction "EMUC1/SOSCO/T1CK/CN0/RC14_60") (pintype "bidirectional+no_connect"))
    )
    (net (code "98") (name "unconnected-(Upic-EMUC3{slash}SCK1{slash}INT0{slash}RF6-Pad45)") (class "Default")
      (node (ref "Upic") (pin "45") (pinfunction "EMUC3/SCK1/INT0/RF6_45") (pintype "bidirectional+no_connect"))
    )
    (net (code "99") (name "unconnected-(Upic-EMUD1{slash}SOSCI{slash}CN1{slash}RC13-Pad59)") (class "Default")
      (node (ref "Upic") (pin "59") (pinfunction "EMUD1/SOSCI/CN1/RC13_59") (pintype "bidirectional+no_connect"))
    )
    (net (code "100") (name "unconnected-(Upic-EMUD2{slash}OC2{slash}RD1-Pad61)") (class "Default")
      (node (ref "Upic") (pin "61") (pinfunction "EMUD2/OC2/RD1_61") (pintype "bidirectional+no_connect"))
    )
    (net (code "101") (name "unconnected-(Upic-EMUD3{slash}SDO1{slash}RF8-Pad43)") (class "Default")
      (node (ref "Upic") (pin "43") (pinfunction "EMUD3/SDO1/RF8_43") (pintype "bidirectional+no_connect"))
    )
    (net (code "102") (name "unconnected-(Upic-IC7{slash}CN20{slash}RD14-Pad37)") (class "Default")
      (node (ref "Upic") (pin "37") (pinfunction "IC7/CN20/RD14_37") (pintype "bidirectional+no_connect"))
    )
    (net (code "103") (name "unconnected-(Upic-IC8{slash}CN21{slash}RD15-Pad38)") (class "Default")
      (node (ref "Upic") (pin "38") (pinfunction "IC8/CN21/RD15_38") (pintype "bidirectional+no_connect"))
    )
    (net (code "104") (name "unconnected-(Upic-OC3{slash}RD2-Pad62)") (class "Default")
      (node (ref "Upic") (pin "62") (pinfunction "OC3/RD2_62") (pintype "bidirectional+no_connect"))
    )
    (net (code "105") (name "unconnected-(Upic-OC4{slash}RD3-Pad63)") (class "Default")
      (node (ref "Upic") (pin "63") (pinfunction "OC4/RD3_63") (pintype "bidirectional+no_connect"))
    )
    (net (code "106") (name "unconnected-(Upic-SDI1{slash}RF7-Pad44)") (class "Default")
      (node (ref "Upic") (pin "44") (pinfunction "SDI1/RF7_44") (pintype "bidirectional+no_connect"))
    )
    (net (code "107") (name "unconnected-(Upic-T2CK{slash}RC1-Pad4)") (class "Default")
      (node (ref "Upic") (pin "4") (pinfunction "T2CK/RC1_4") (pintype "bidirectional+no_connect"))
    )
    (net (code "108") (name "unconnected-(Upic-T4CK{slash}RC3-Pad5)") (class "Default")
      (node (ref "Upic") (pin "5") (pinfunction "T4CK/RC3_5") (pintype "bidirectional+no_connect"))
    )
  )
)
